# Power_Distribution_-_Spares.net
KiCad netlist of a schematic drawn in Altium Designer
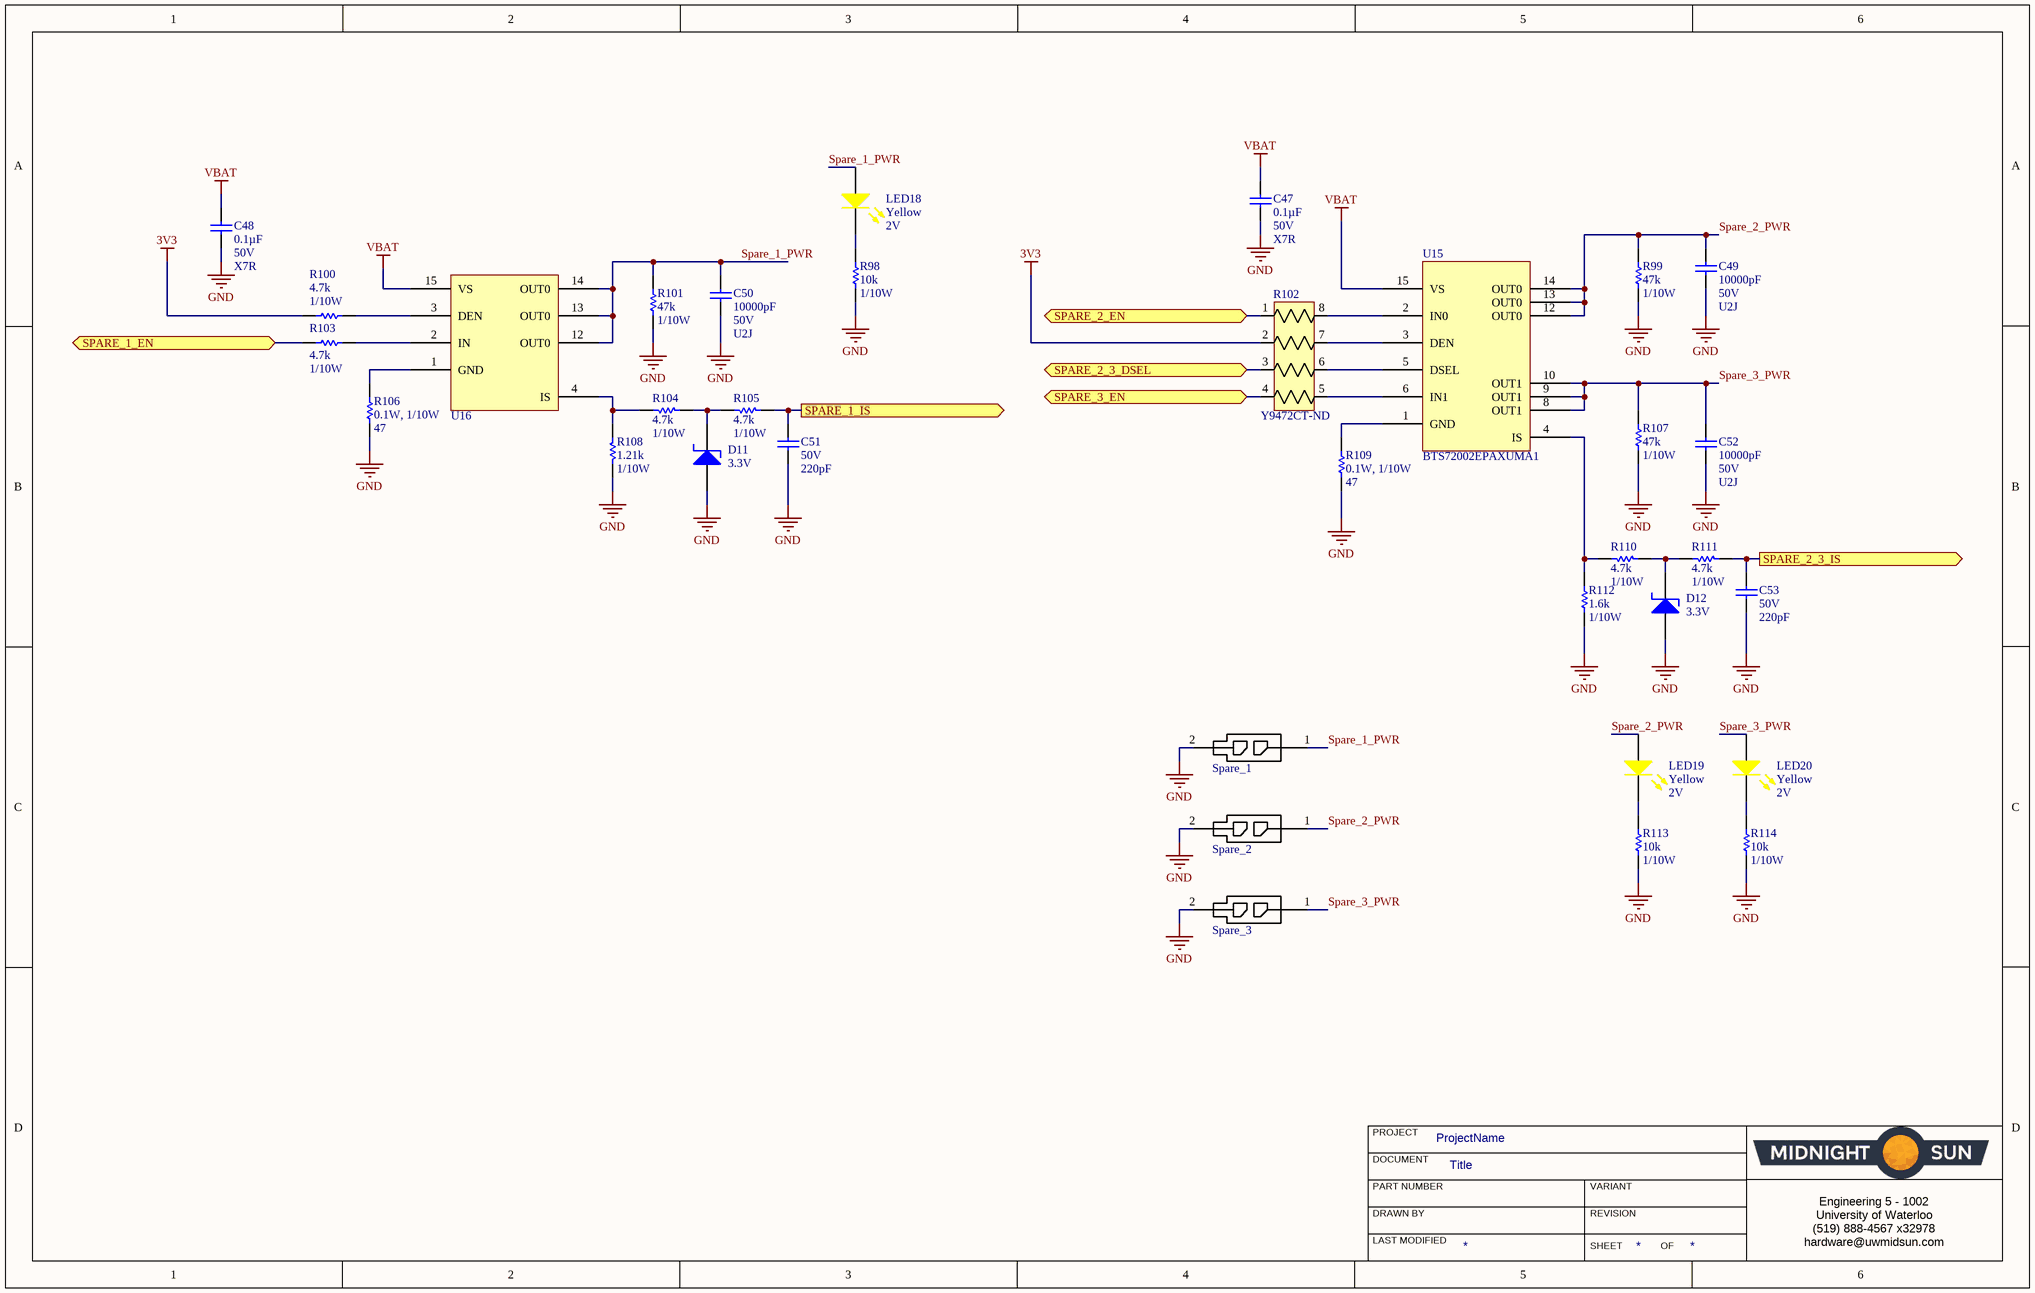
[diagram p0: Power Distribution - Spares.SchDoc]

(export (version "E")
  (design (tool "Eeschema 10.0.6"))
  (components
    (comp (ref "C47")
      (value "CAP CER 0.1UF 50V 10% X7R 0603")
      (footprint "CAP, 0603")
      (description "0.10µF ±10% 50V Ceramic Capacitor X7R 0603 (1608 Metric)")
      (fields
        (field (name "TOLERANCE") "±10%")
        (field (name "CAPACITANCE") "0.1µF")
        (field (name "VOLTAGE") "50V")
        (field (name "TEMPERATURE COEFFICIENT") "X7R")
      )
      (libsource (lib "Schematic Diagrams") (part "CAP CER 0.1UF 50V 10% X7R 0603"))
    )
    (comp (ref "C48")
      (value "CAP CER 0.1UF 50V 10% X7R 0603")
      (footprint "CAP, 0603")
      (description "0.10µF ±10% 50V Ceramic Capacitor X7R 0603 (1608 Metric)")
      (fields
        (field (name "TOLERANCE") "±10%")
        (field (name "CAPACITANCE") "0.1µF")
        (field (name "VOLTAGE") "50V")
        (field (name "TEMPERATURE COEFFICIENT") "X7R")
      )
      (libsource (lib "Schematic Diagrams") (part "CAP CER 0.1UF 50V 10% X7R 0603"))
    )
    (comp (ref "C49")
      (value "CAP CER 10nF 50V 5% X7R 0603")
      (footprint "CAP, 0603")
      (description "10000pF ±5% 50V Ceramic Capacitor U2J 0603 (1608 Metric)")
      (fields
        (field (name "TOLERANCE") "±5%")
        (field (name "CAPACITANCE") "10000pF")
        (field (name "VOLTAGE") "50V")
        (field (name "TEMPERATURE COEFFICIENT") "U2J")
      )
      (libsource (lib "Schematic Diagrams") (part "CAP CER 10nF 50V 5% X7R 0603"))
    )
    (comp (ref "C50")
      (value "CAP CER 10nF 50V 5% X7R 0603")
      (footprint "CAP, 0603")
      (description "10000pF ±5% 50V Ceramic Capacitor U2J 0603 (1608 Metric)")
      (fields
        (field (name "TOLERANCE") "±5%")
        (field (name "CAPACITANCE") "10000pF")
        (field (name "VOLTAGE") "50V")
        (field (name "TEMPERATURE COEFFICIENT") "U2J")
      )
      (libsource (lib "Schematic Diagrams") (part "CAP CER 10nF 50V 5% X7R 0603"))
    )
    (comp (ref "C51")
      (value "CAP CER 220PF 50V C0G/NP0 0603")
      (footprint "CAP, 0603")
      (description "220pF ±5% 50V Ceramic Capacitor C0G, NP0 0603 (1608 Metric)")
      (fields
        (field (name "MANUFACTURER") "KEMET")
        (field (name "TOLERANCE") "5%")
        (field (name "VOLTAGE RATING") "50V")
        (field (name "CAPACITANCE") "220pF")
      )
      (libsource (lib "Schematic Diagrams") (part "CAP CER 220PF 50V C0G/NP0 0603"))
    )
    (comp (ref "C52")
      (value "CAP CER 10nF 50V 5% X7R 0603")
      (footprint "CAP, 0603")
      (description "10000pF ±5% 50V Ceramic Capacitor U2J 0603 (1608 Metric)")
      (fields
        (field (name "TOLERANCE") "±5%")
        (field (name "CAPACITANCE") "10000pF")
        (field (name "VOLTAGE") "50V")
        (field (name "TEMPERATURE COEFFICIENT") "U2J")
      )
      (libsource (lib "Schematic Diagrams") (part "CAP CER 10nF 50V 5% X7R 0603"))
    )
    (comp (ref "C53")
      (value "CAP CER 220PF 50V C0G/NP0 0603")
      (footprint "CAP, 0603")
      (description "220pF ±5% 50V Ceramic Capacitor C0G, NP0 0603 (1608 Metric)")
      (fields
        (field (name "MANUFACTURER") "KEMET")
        (field (name "TOLERANCE") "5%")
        (field (name "VOLTAGE RATING") "50V")
        (field (name "CAPACITANCE") "220pF")
      )
      (libsource (lib "Schematic Diagrams") (part "CAP CER 220PF 50V C0G/NP0 0603"))
    )
    (comp (ref "D11")
      (value "DIODE ZENER 3.3V 200MW SOD323")
      (footprint "sod-323")
      (description "Zener Diode 3.3V 200mW ±5% Surface Mount SOD-323")
      (fields (field (name "VOLTAGE") "3.3V"))
      (libsource (lib "Schematic Diagrams") (part "DIODE ZENER 3.3V 200MW SOD323"))
    )
    (comp (ref "D12")
      (value "DIODE ZENER 3.3V 200MW SOD323")
      (footprint "sod-323")
      (description "Zener Diode 3.3V 200mW ±5% Surface Mount SOD-323")
      (fields (field (name "VOLTAGE") "3.3V"))
      (libsource (lib "Schematic Diagrams") (part "DIODE ZENER 3.3V 200MW SOD323"))
    )
    (comp (ref "LED18")
      (value "LED YELLOW CLEAR 2.1V 0603")
      (footprint "LED_0603")
      (description "Yellow 590nm LED Indication - Discrete 2V 0603 (1608 Metric)")
      (fields
        (field (name "MANUFACTURER") "Wurth Electronics Inc.")
        (field (name "MANUFACTURER PART NUMBER") "150060YS75000")
        (field (name "COLOR") "Yellow")
        (field (name "VOLTAGE - FORWARD (VF) (TYP)") "2V")
      )
      (libsource (lib "Schematic Diagrams") (part "LED YELLOW CLEAR 2.1V 0603"))
    )
    (comp (ref "LED19")
      (value "LED YELLOW CLEAR 2.1V 0603")
      (footprint "LED_0603")
      (description "Yellow 590nm LED Indication - Discrete 2V 0603 (1608 Metric)")
      (fields
        (field (name "MANUFACTURER") "Wurth Electronics Inc.")
        (field (name "MANUFACTURER PART NUMBER") "150060YS75000")
        (field (name "COLOR") "Yellow")
        (field (name "VOLTAGE - FORWARD (VF) (TYP)") "2V")
      )
      (libsource (lib "Schematic Diagrams") (part "LED YELLOW CLEAR 2.1V 0603"))
    )
    (comp (ref "LED20")
      (value "LED YELLOW CLEAR 2.1V 0603")
      (footprint "LED_0603")
      (description "Yellow 590nm LED Indication - Discrete 2V 0603 (1608 Metric)")
      (fields
        (field (name "MANUFACTURER") "Wurth Electronics Inc.")
        (field (name "MANUFACTURER PART NUMBER") "150060YS75000")
        (field (name "COLOR") "Yellow")
        (field (name "VOLTAGE - FORWARD (VF) (TYP)") "2V")
      )
      (libsource (lib "Schematic Diagrams") (part "LED YELLOW CLEAR 2.1V 0603"))
    )
    (comp (ref "R98")
      (value "RES 10K OHM 1% 1/10W 0603")
      (footprint "RES, 0603")
      (description "RES SMD 10K OHM 1% 1/10W 0603")
      (fields
        (field (name "TOLERANCE") "±1%")
        (field (name "RESISTANCE") "10k")
        (field (name "POWER") "1/10W")
      )
      (libsource (lib "Schematic Diagrams") (part "RES 10K OHM 1% 1/10W 0603"))
    )
    (comp (ref "R99")
      (value "RES 47K OHM 1% 1/10W 0603")
      (footprint "RES, 0603")
      (description "47 kOhms ±1% 0.1W, 1/10W Chip Resistor 0603 (1608 Metric) Automotive AEC-Q200 Thick Film")
      (fields
        (field (name "MANUFACTURER") "Panasonic")
        (field (name "MANUFACTURER PART NUMBER") "ERJ3EKF4702V")
        (field (name "RESISTANCE") "47k")
        (field (name "POWER RATING") "1/10W")
      )
      (libsource (lib "Schematic Diagrams") (part "RES 47K OHM 1% 1/10W 0603"))
    )
    (comp (ref "R100")
      (value "RES 4.7K OHM 1% 1/10W 0603")
      (footprint "RES, 0603")
      (description "4.7k Ohm ±1% 0.1W, 1/10W Chip Resistor 0603 (1608 Metric) Moisture Resistant Thick Film")
      (fields
        (field (name "TOLERANCE") "±1%")
        (field (name "RESISTANCE (OHMS)") "4.7k")
        (field (name "POWER (WATTS)") "1/10W")
      )
      (libsource (lib "Schematic Diagrams") (part "RES 4.7K OHM 1% 1/10W 0603"))
    )
    (comp (ref "R101")
      (value "RES 47K OHM 1% 1/10W 0603")
      (footprint "RES, 0603")
      (description "47 kOhms ±1% 0.1W, 1/10W Chip Resistor 0603 (1608 Metric) Automotive AEC-Q200 Thick Film")
      (fields
        (field (name "MANUFACTURER") "Panasonic")
        (field (name "MANUFACTURER PART NUMBER") "ERJ3EKF4702V")
        (field (name "RESISTANCE") "47k")
        (field (name "POWER RATING") "1/10W")
      )
      (libsource (lib "Schematic Diagrams") (part "RES 47K OHM 1% 1/10W 0603"))
    )
    (comp (ref "R102")
      (value "RES ARRAY 4 RES 4.7K OHM 1206")
      (footprint "RES ARRAY 4RES 1206")
      (fields (field (name "TOLERANCE") "±5%") (field (name "SUPPLIER PART NUMBER 1") "Y9472CT-ND"))
      (libsource (lib "Schematic Diagrams") (part "RES ARRAY 4 RES 4.7K OHM 1206"))
    )
    (comp (ref "R103")
      (value "RES 4.7K OHM 1% 1/10W 0603")
      (footprint "RES, 0603")
      (description "4.7k Ohm ±1% 0.1W, 1/10W Chip Resistor 0603 (1608 Metric) Moisture Resistant Thick Film")
      (fields
        (field (name "TOLERANCE") "±1%")
        (field (name "RESISTANCE (OHMS)") "4.7k")
        (field (name "POWER (WATTS)") "1/10W")
      )
      (libsource (lib "Schematic Diagrams") (part "RES 4.7K OHM 1% 1/10W 0603"))
    )
    (comp (ref "R104")
      (value "RES 4.7K OHM 1% 1/10W 0603")
      (footprint "RES, 0603")
      (description "4.7k Ohm ±1% 0.1W, 1/10W Chip Resistor 0603 (1608 Metric) Moisture Resistant Thick Film")
      (fields
        (field (name "TOLERANCE") "±1%")
        (field (name "RESISTANCE (OHMS)") "4.7k")
        (field (name "POWER (WATTS)") "1/10W")
      )
      (libsource (lib "Schematic Diagrams") (part "RES 4.7K OHM 1% 1/10W 0603"))
    )
    (comp (ref "R105")
      (value "RES 4.7K OHM 1% 1/10W 0603")
      (footprint "RES, 0603")
      (description "4.7k Ohm ±1% 0.1W, 1/10W Chip Resistor 0603 (1608 Metric) Moisture Resistant Thick Film")
      (fields
        (field (name "TOLERANCE") "±1%")
        (field (name "RESISTANCE (OHMS)") "4.7k")
        (field (name "POWER (WATTS)") "1/10W")
      )
      (libsource (lib "Schematic Diagrams") (part "RES 4.7K OHM 1% 1/10W 0603"))
    )
    (comp (ref "R106")
      (value "RES SMD 47 OHM 1% 1/10W 0603")
      (footprint "RES, 0603")
      (fields
        (field (name "TOLERANCE") "±1%")
        (field (name "POWER (WATTS)") "0.1W, 1/10W")
        (field (name "VALUES") "47")
      )
      (libsource (lib "Schematic Diagrams") (part "RES SMD 47 OHM 1% 1/10W 0603"))
    )
    (comp (ref "R107")
      (value "RES 47K OHM 1% 1/10W 0603")
      (footprint "RES, 0603")
      (description "47 kOhms ±1% 0.1W, 1/10W Chip Resistor 0603 (1608 Metric) Automotive AEC-Q200 Thick Film")
      (fields
        (field (name "MANUFACTURER") "Panasonic")
        (field (name "MANUFACTURER PART NUMBER") "ERJ3EKF4702V")
        (field (name "RESISTANCE") "47k")
        (field (name "POWER RATING") "1/10W")
      )
      (libsource (lib "Schematic Diagrams") (part "RES 47K OHM 1% 1/10W 0603"))
    )
    (comp (ref "R108")
      (value "RES 1.21K OHM 1% 1/10W 0603")
      (footprint "RES, 0603")
      (description "1.21k Ohm ±1% 0.1W, 1/10W Chip Resistor 0603 (1608 Metric) Moisture Resistant Thick Film")
      (fields
        (field (name "TOLERANCE") "±1%")
        (field (name "RESISTANCE") "1.21k")
        (field (name "POWER") "1/10W")
      )
      (libsource (lib "Schematic Diagrams") (part "RES 1.21K OHM 1% 1/10W 0603"))
    )
    (comp (ref "R109")
      (value "RES SMD 47 OHM 1% 1/10W 0603")
      (footprint "RES, 0603")
      (fields
        (field (name "TOLERANCE") "±1%")
        (field (name "POWER (WATTS)") "0.1W, 1/10W")
        (field (name "VALUES") "47")
      )
      (libsource (lib "Schematic Diagrams") (part "RES SMD 47 OHM 1% 1/10W 0603"))
    )
    (comp (ref "R110")
      (value "RES 4.7K OHM 1% 1/10W 0603")
      (footprint "RES, 0603")
      (description "4.7k Ohm ±1% 0.1W, 1/10W Chip Resistor 0603 (1608 Metric) Moisture Resistant Thick Film")
      (fields
        (field (name "TOLERANCE") "±1%")
        (field (name "RESISTANCE (OHMS)") "4.7k")
        (field (name "POWER (WATTS)") "1/10W")
      )
      (libsource (lib "Schematic Diagrams") (part "RES 4.7K OHM 1% 1/10W 0603"))
    )
    (comp (ref "R111")
      (value "RES 4.7K OHM 1% 1/10W 0603")
      (footprint "RES, 0603")
      (description "4.7k Ohm ±1% 0.1W, 1/10W Chip Resistor 0603 (1608 Metric) Moisture Resistant Thick Film")
      (fields
        (field (name "TOLERANCE") "±1%")
        (field (name "RESISTANCE (OHMS)") "4.7k")
        (field (name "POWER (WATTS)") "1/10W")
      )
      (libsource (lib "Schematic Diagrams") (part "RES 4.7K OHM 1% 1/10W 0603"))
    )
    (comp (ref "R112")
      (value "RES 1.6K OHM 1% 1/10W 0603")
      (footprint "RES, 0603")
      (description "1.6 kOhms ±1% 0.1W, 1/10W Chip Resistor 0603 (1608 Metric) Moisture Resistant Thick Film")
      (fields
        (field (name "MANUFACTURER") "Yageo")
        (field (name "MANUFACTURER PART NUMBER") "RC0603FR-071K6L")
        (field (name "RESISTANCE") "1.6k")
        (field (name "POWER RATING") "1/10W")
      )
      (libsource (lib "Schematic Diagrams") (part "RES 1.6K OHM 1% 1/10W 0603"))
    )
    (comp (ref "R113")
      (value "RES 10K OHM 1% 1/10W 0603")
      (footprint "RES, 0603")
      (description "RES SMD 10K OHM 1% 1/10W 0603")
      (fields
        (field (name "TOLERANCE") "±1%")
        (field (name "RESISTANCE") "10k")
        (field (name "POWER") "1/10W")
      )
      (libsource (lib "Schematic Diagrams") (part "RES 10K OHM 1% 1/10W 0603"))
    )
    (comp (ref "R114")
      (value "RES 10K OHM 1% 1/10W 0603")
      (footprint "RES, 0603")
      (description "RES SMD 10K OHM 1% 1/10W 0603")
      (fields
        (field (name "TOLERANCE") "±1%")
        (field (name "RESISTANCE") "10k")
        (field (name "POWER") "1/10W")
      )
      (libsource (lib "Schematic Diagrams") (part "RES 10K OHM 1% 1/10W 0603"))
    )
    (comp (ref "Spare_1")
      (value "CONN 2POS MICRO-FIT 3mm")
      (footprint "CONN, 2POS MICRO-FIT")
      (description "Connector Header Through Hole 2 position")
      (fields (field (name "MANUFACTURER") "Molex") (field (name "MANUFACTURER PART NUMBER") "43045-0227"))
      (libsource (lib "Schematic Diagrams") (part "CONN 2POS MICRO-FIT 3mm"))
    )
    (comp (ref "Spare_2")
      (value "CONN 2POS MICRO-FIT 3mm")
      (footprint "CONN, 2POS MICRO-FIT")
      (description "Connector Header Through Hole 2 position")
      (fields (field (name "MANUFACTURER") "Molex") (field (name "MANUFACTURER PART NUMBER") "43045-0227"))
      (libsource (lib "Schematic Diagrams") (part "CONN 2POS MICRO-FIT 3mm"))
    )
    (comp (ref "Spare_3")
      (value "CONN 2POS MICRO-FIT 3mm")
      (footprint "CONN, 2POS MICRO-FIT")
      (description "Connector Header Through Hole 2 position")
      (fields (field (name "MANUFACTURER") "Molex") (field (name "MANUFACTURER PART NUMBER") "43045-0227"))
      (libsource (lib "Schematic Diagrams") (part "CONN 2POS MICRO-FIT 3mm"))
    )
    (comp (ref "U15")
      (value "IC LOAD SWITCH BTS7200-2EPA PG-TSDSO-14_1")
      (footprint "IC LOAD SWITCH PG-TSDSO-14-22")
      (description "Power Switch/Driver 1:1 N-Channel 1.2A PG-TSDSO-14-22")
      (fields
        (field (name "MANUFACTURER") "Infineon")
        (field (name "MANUFACTURER PART NUMBER") "BTS72002EPAXUMA1")
      )
      (libsource (lib "Schematic Diagrams") (part "IC LOAD SWITCH BTS7200-2EPA PG-TSDSO-14_1"))
    )
    (comp (ref "U16")
      (value "IC LOAD SWITCH BTS70401EPA PG-TSDSO-14-22")
      (footprint "IC LOAD SWITCH PG-TSDSO-14-22")
      (description "Power Switch/Driver 1:1 N-Channel 4.5A PG-TSDSO-14-22")
      (fields
        (field (name "MANUFACTURER") "Infineon")
        (field (name "MANUFACTURER PART NUMBER") "BTS70401EPAXUMA1")
      )
      (libsource (lib "Schematic Diagrams") (part "IC LOAD SWITCH BTS70401EPA PG-TSDSO-14-22"))
    )
  )
  (nets
    (net (code "1") (name "/SPARE_1_EN") (class "Default")
      (node (ref "R103") (pin "1") (pinfunction "1_1") (pintype "passive"))
    )
    (net (code "2") (name "/SPARE_1_IS") (class "Default")
      (node (ref "C51") (pin "1") (pinfunction "1_1") (pintype "passive"))
      (node (ref "R105") (pin "1") (pinfunction "1_1") (pintype "passive"))
    )
    (net (code "3") (name "/SPARE_2_3_DSEL") (class "Default")
      (node (ref "R102") (pin "3") (pinfunction "3_3") (pintype "passive"))
    )
    (net (code "4") (name "/SPARE_2_3_IS") (class "Default")
      (node (ref "C53") (pin "1") (pinfunction "1_1") (pintype "passive"))
      (node (ref "R111") (pin "1") (pinfunction "1_1") (pintype "passive"))
    )
    (net (code "5") (name "/SPARE_2_EN") (class "Default")
      (node (ref "R102") (pin "1") (pinfunction "1_1") (pintype "passive"))
    )
    (net (code "6") (name "/SPARE_3_EN") (class "Default")
      (node (ref "R102") (pin "4") (pinfunction "4_4") (pintype "passive"))
    )
    (net (code "7") (name "/Spare_1_PWR") (class "Default")
      (node (ref "C50") (pin "1") (pinfunction "1_1") (pintype "passive"))
      (node (ref "LED18") (pin "1") (pinfunction "A_1") (pintype "passive"))
      (node (ref "R101") (pin "1") (pinfunction "1_1") (pintype "passive"))
      (node (ref "Spare_1") (pin "1") (pinfunction "1_1") (pintype "passive"))
      (node (ref "U16") (pin "12") (pinfunction "OUT0_12") (pintype "passive"))
      (node (ref "U16") (pin "13") (pinfunction "OUT0_13") (pintype "passive"))
      (node (ref "U16") (pin "14") (pinfunction "OUT0_14") (pintype "passive"))
    )
    (net (code "8") (name "/Spare_2_PWR") (class "Default")
      (node (ref "C49") (pin "1") (pinfunction "1_1") (pintype "passive"))
      (node (ref "LED19") (pin "1") (pinfunction "A_1") (pintype "passive"))
      (node (ref "R99") (pin "1") (pinfunction "1_1") (pintype "passive"))
      (node (ref "Spare_2") (pin "1") (pinfunction "1_1") (pintype "passive"))
      (node (ref "U15") (pin "12") (pinfunction "OUT0_12") (pintype "passive"))
      (node (ref "U15") (pin "13") (pinfunction "OUT0_13") (pintype "passive"))
      (node (ref "U15") (pin "14") (pinfunction "OUT0_14") (pintype "passive"))
    )
    (net (code "9") (name "/Spare_3_PWR") (class "Default")
      (node (ref "C52") (pin "1") (pinfunction "1_1") (pintype "passive"))
      (node (ref "LED20") (pin "1") (pinfunction "A_1") (pintype "passive"))
      (node (ref "R107") (pin "1") (pinfunction "1_1") (pintype "passive"))
      (node (ref "Spare_3") (pin "1") (pinfunction "1_1") (pintype "passive"))
      (node (ref "U15") (pin "10") (pinfunction "OUT1_10") (pintype "passive"))
      (node (ref "U15") (pin "8") (pinfunction "OUT1_8") (pintype "passive"))
      (node (ref "U15") (pin "9") (pinfunction "OUT1_9") (pintype "passive"))
    )
    (net (code "10") (name "3V3") (class "Default")
      (node (ref "R100") (pin "1") (pinfunction "1_1") (pintype "passive"))
      (node (ref "R102") (pin "2") (pinfunction "2_2") (pintype "passive"))
    )
    (net (code "11") (name "GND") (class "Default")
      (node (ref "C47") (pin "2") (pinfunction "2_2") (pintype "passive"))
      (node (ref "C48") (pin "2") (pinfunction "2_2") (pintype "passive"))
      (node (ref "C49") (pin "2") (pinfunction "2_2") (pintype "passive"))
      (node (ref "C50") (pin "2") (pinfunction "2_2") (pintype "passive"))
      (node (ref "C51") (pin "2") (pinfunction "2_2") (pintype "passive"))
      (node (ref "C52") (pin "2") (pinfunction "2_2") (pintype "passive"))
      (node (ref "C53") (pin "2") (pinfunction "2_2") (pintype "passive"))
      (node (ref "D11") (pin "1") (pinfunction "A_1") (pintype "passive"))
      (node (ref "D12") (pin "1") (pinfunction "A_1") (pintype "passive"))
      (node (ref "R101") (pin "2") (pinfunction "2_2") (pintype "passive"))
      (node (ref "R106") (pin "2") (pinfunction "2_2") (pintype "passive"))
      (node (ref "R107") (pin "2") (pinfunction "2_2") (pintype "passive"))
      (node (ref "R108") (pin "2") (pinfunction "2_2") (pintype "passive"))
      (node (ref "R109") (pin "2") (pinfunction "2_2") (pintype "passive"))
      (node (ref "R112") (pin "2") (pinfunction "2_2") (pintype "passive"))
      (node (ref "R113") (pin "2") (pinfunction "2_2") (pintype "passive"))
      (node (ref "R114") (pin "2") (pinfunction "2_2") (pintype "passive"))
      (node (ref "R98") (pin "2") (pinfunction "2_2") (pintype "passive"))
      (node (ref "R99") (pin "2") (pinfunction "2_2") (pintype "passive"))
      (node (ref "Spare_1") (pin "2") (pinfunction "2_2") (pintype "passive"))
      (node (ref "Spare_2") (pin "2") (pinfunction "2_2") (pintype "passive"))
      (node (ref "Spare_3") (pin "2") (pinfunction "2_2") (pintype "passive"))
    )
    (net (code "12") (name "Net-(D11-K)") (class "Default")
      (node (ref "D11") (pin "2") (pinfunction "K_2") (pintype "passive"))
      (node (ref "R104") (pin "1") (pinfunction "1_1") (pintype "passive"))
      (node (ref "R105") (pin "2") (pinfunction "2_2") (pintype "passive"))
    )
    (net (code "13") (name "Net-(D12-K)") (class "Default")
      (node (ref "D12") (pin "2") (pinfunction "K_2") (pintype "passive"))
      (node (ref "R110") (pin "1") (pinfunction "1_1") (pintype "passive"))
      (node (ref "R111") (pin "2") (pinfunction "2_2") (pintype "passive"))
    )
    (net (code "14") (name "Net-(LED18-K)") (class "Default")
      (node (ref "LED18") (pin "2") (pinfunction "K_2") (pintype "passive"))
      (node (ref "R98") (pin "1") (pinfunction "1_1") (pintype "passive"))
    )
    (net (code "15") (name "Net-(LED19-K)") (class "Default")
      (node (ref "LED19") (pin "2") (pinfunction "K_2") (pintype "passive"))
      (node (ref "R113") (pin "1") (pinfunction "1_1") (pintype "passive"))
    )
    (net (code "16") (name "Net-(LED20-K)") (class "Default")
      (node (ref "LED20") (pin "2") (pinfunction "K_2") (pintype "passive"))
      (node (ref "R114") (pin "1") (pinfunction "1_1") (pintype "passive"))
    )
    (net (code "17") (name "Net-(U15-DEN)") (class "Default")
      (node (ref "R102") (pin "7") (pinfunction "7_7") (pintype "passive"))
      (node (ref "U15") (pin "3") (pinfunction "DEN_3") (pintype "passive"))
    )
    (net (code "18") (name "Net-(U15-DSEL)") (class "Default")
      (node (ref "R102") (pin "6") (pinfunction "6_6") (pintype "passive"))
      (node (ref "U15") (pin "5") (pinfunction "DSEL_5") (pintype "passive"))
    )
    (net (code "19") (name "Net-(U15-GND)") (class "Default")
      (node (ref "R109") (pin "1") (pinfunction "1_1") (pintype "passive"))
      (node (ref "U15") (pin "1") (pinfunction "GND_1") (pintype "passive"))
    )
    (net (code "20") (name "Net-(U15-IN0)") (class "Default")
      (node (ref "R102") (pin "8") (pinfunction "8_8") (pintype "passive"))
      (node (ref "U15") (pin "2") (pinfunction "IN0_2") (pintype "passive"))
    )
    (net (code "21") (name "Net-(U15-IN1)") (class "Default")
      (node (ref "R102") (pin "5") (pinfunction "5_5") (pintype "passive"))
      (node (ref "U15") (pin "6") (pinfunction "IN1_6") (pintype "passive"))
    )
    (net (code "22") (name "Net-(U15-IS)") (class "Default")
      (node (ref "R110") (pin "2") (pinfunction "2_2") (pintype "passive"))
      (node (ref "R112") (pin "1") (pinfunction "1_1") (pintype "passive"))
      (node (ref "U15") (pin "4") (pinfunction "IS_4") (pintype "passive"))
    )
    (net (code "23") (name "Net-(U16-DEN)") (class "Default")
      (node (ref "R100") (pin "2") (pinfunction "2_2") (pintype "passive"))
      (node (ref "U16") (pin "3") (pinfunction "DEN_3") (pintype "passive"))
    )
    (net (code "24") (name "Net-(U16-GND)") (class "Default")
      (node (ref "R106") (pin "1") (pinfunction "1_1") (pintype "passive"))
      (node (ref "U16") (pin "1") (pinfunction "GND_1") (pintype "passive"))
    )
    (net (code "25") (name "Net-(U16-IN)") (class "Default")
      (node (ref "R103") (pin "2") (pinfunction "2_2") (pintype "passive"))
      (node (ref "U16") (pin "2") (pinfunction "IN_2") (pintype "passive"))
    )
    (net (code "26") (name "Net-(U16-IS)") (class "Default")
      (node (ref "R104") (pin "2") (pinfunction "2_2") (pintype "passive"))
      (node (ref "R108") (pin "1") (pinfunction "1_1") (pintype "passive"))
      (node (ref "U16") (pin "4") (pinfunction "IS_4") (pintype "passive"))
    )
    (net (code "27") (name "VBAT") (class "Default")
      (node (ref "C47") (pin "1") (pinfunction "1_1") (pintype "passive"))
      (node (ref "C48") (pin "1") (pinfunction "1_1") (pintype "passive"))
      (node (ref "U15") (pin "15") (pinfunction "VS_15") (pintype "passive"))
      (node (ref "U16") (pin "15") (pinfunction "VS_15") (pintype "passive"))
    )
  )
)
